# esquema.net
KiCad netlist of a schematic drawn in EAGLE
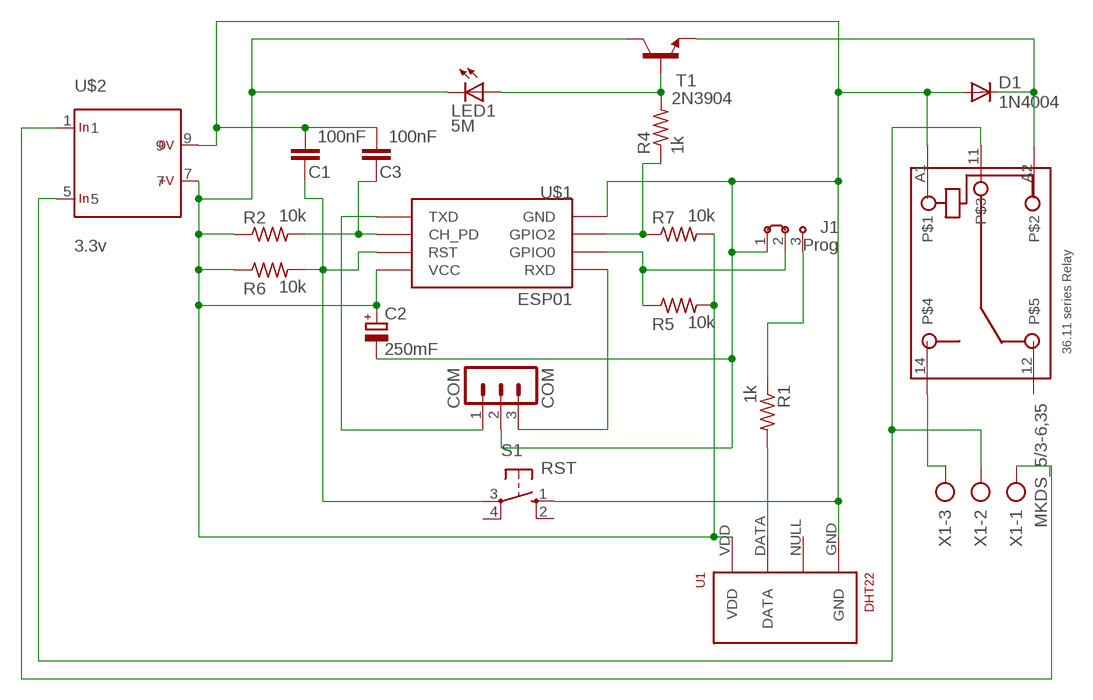
[diagram p0: schematic, sheet 1]

(export (version "E")
  (design (tool "Eeschema 10.0.6"))
  (components
    (comp (ref "C1")
      (value "100nF")
      (footprint "eagle-import:CAP-PTH-SMALL-KIT")
      (libsource (lib "eagle-import") (part "0.1UF-50V-20%(PTH)KIT-EZ"))
    )
    (comp (ref "C2")
      (value "250mF")
      (footprint "eagle-import:E2-5")
      (libsource (lib "eagle-import") (part "CPOL-EUE2-5"))
    )
    (comp (ref "C3")
      (value "100nF")
      (footprint "eagle-import:CAP-PTH-SMALL-KIT")
      (libsource (lib "eagle-import") (part "0.1UF-50V-20%(PTH)KIT-EZ"))
    )
    (comp (ref "COM")
      (value "COM")
      (footprint "eagle-import:MA03-1")
      (fields
        (field (name "MF") "MOLEX")
        (field (name "MPN") "47053-1000")
        (field (name "OC_FARNELL") "2313705")
      )
      (libsource (lib "eagle-import") (part "MA03-1"))
    )
    (comp (ref "D1")
      (value "1N4004")
      (footprint "eagle-import:DO41-10")
      (fields (field (name "MF") "VISHAY") (field (name "MPN") "1N4004-E3/54"))
      (libsource (lib "eagle-import") (part "1N4004"))
    )
    (comp (ref "J1")
      (value "Prog")
      (footprint "eagle-import:04C")
      (libsource (lib "eagle-import") (part "J2X2MM"))
    )
    (comp (ref "K1")
      (value "36.11")
      (footprint "eagle-import:36.11")
      (libsource (lib "eagle-import") (part "36.11"))
    )
    (comp (ref "LED1")
      (value "5M")
      (footprint "eagle-import:LED3MM")
      (fields (field (name "MF") "VISHAY") (field (name "MPN") "HVR3700001504JA100"))
      (libsource (lib "eagle-import") (part "LED3MM"))
    )
    (comp (ref "R1")
      (value "1k")
      (footprint "eagle-import:0204_5")
      (fields (field (name "MF") "MULTICOMP") (field (name "MPN") "MCF 0.25W 1K"))
      (libsource (lib "eagle-import") (part "R-US_0204/5"))
    )
    (comp (ref "R2")
      (value "10k")
      (footprint "eagle-import:0204_5")
      (fields (field (name "MF") "MULTICOMP") (field (name "MPN") "MCF 0.25W 10K"))
      (libsource (lib "eagle-import") (part "R-US_0204/5"))
    )
    (comp (ref "R4")
      (value "1k")
      (footprint "eagle-import:0204_5")
      (fields (field (name "MF") "MULTICOMP") (field (name "MPN") "MCF 0.25W 10K"))
      (libsource (lib "eagle-import") (part "R-US_0204/5"))
    )
    (comp (ref "R5")
      (value "10k")
      (footprint "eagle-import:0204_5")
      (fields (field (name "MF") "MULTICOMP") (field (name "MPN") "MCF 0.25W 10K"))
      (libsource (lib "eagle-import") (part "R-US_0204/5"))
    )
    (comp (ref "R6")
      (value "10k")
      (footprint "eagle-import:0204_5")
      (fields (field (name "MF") "MULTICOMP") (field (name "MPN") "MCF 0.25W 10K"))
      (libsource (lib "eagle-import") (part "R-US_0204/5"))
    )
    (comp (ref "R7")
      (value "10k")
      (footprint "eagle-import:0204_5")
      (fields (field (name "MF") "MULTICOMP") (field (name "MPN") "MCF 0.25W 10K"))
      (libsource (lib "eagle-import") (part "R-US_0204/5"))
    )
    (comp (ref "S1")
      (value "RST")
      (footprint "eagle-import:B3F-10XX")
      (fields (field (name "MPN") "B3F-1000"))
      (libsource (lib "eagle-import") (part "10-XX"))
    )
    (comp (ref "T1")
      (value "2N3904")
      (footprint "eagle-import:TO92")
      (fields (field (name "MF") "MULTICOMP"))
      (libsource (lib "eagle-import") (part "2N3904"))
    )
    (comp (ref "U$1")
      (value "ESP01")
      (footprint "eagle-import:ESP01")
      (libsource (lib "eagle-import") (part "ESP01"))
    )
    (comp (ref "U$2")
      (value "3.3v")
      (footprint "eagle-import:1")
      (fields (field (name "MF") "MYRRA") (field (name "MPN") "47121"))
      (libsource (lib "eagle-import") (part "SINGLE"))
    )
    (comp (ref "U1")
      (value "DHT22")
      (footprint "eagle-import:RHT03_DHT-22")
      (libsource (lib "eagle-import") (part "RHT03_DHT-22_AM2302"))
    )
    (comp (ref "X1")
      (value "MKDS_5/3-6,35")
      (footprint "eagle-import:MKDS_5_3-635")
      (fields (field (name "MF") "FARNELL") (field (name "MPN") "1714968"))
      (libsource (lib "eagle-import") (part "MKDS_5/3-6,35"))
    )
  )
  (nets
    (net (code "1") (name "Net-(C3-Pad1)") (class "Default")
      (node (ref "C3") (pin "1") (pinfunction "1_1") (pintype "passive"))
      (node (ref "R2") (pin "2") (pinfunction "2_2") (pintype "passive"))
      (node (ref "U$1") (pin "CH_PD") (pinfunction "CH_PD_CH_PD") (pintype "bidirectional"))
    )
    (net (code "2") (name "Net-(J1-Pad2)") (class "Default")
      (node (ref "J1") (pin "2") (pinfunction "2_2") (pintype "passive"))
      (node (ref "R5") (pin "1") (pinfunction "1_1") (pintype "passive"))
      (node (ref "U$1") (pin "GPIO0") (pinfunction "GPIO0_GPIO0") (pintype "bidirectional"))
    )
    (net (code "3") (name "Net-(J1-Pad3)") (class "Default")
      (node (ref "J1") (pin "3") (pinfunction "3_3") (pintype "passive"))
      (node (ref "R1") (pin "1") (pinfunction "1_1") (pintype "passive"))
    )
    (net (code "4") (name "Net-(K1-P$1)") (class "Default")
      (node (ref "C1") (pin "2") (pinfunction "2_2") (pintype "passive"))
      (node (ref "C2") (pin "-") (pinfunction "-_-") (pintype "passive"))
      (node (ref "C3") (pin "2") (pinfunction "2_2") (pintype "passive"))
      (node (ref "COM") (pin "2") (pinfunction "2_2") (pintype "passive"))
      (node (ref "D1") (pin "A") (pinfunction "A_A") (pintype "passive"))
      (node (ref "J1") (pin "1") (pinfunction "1_1") (pintype "passive"))
      (node (ref "K1") (pin "A1") (pinfunction "P$1_A1") (pintype "passive"))
      (node (ref "S1") (pin "1") (pinfunction "S_1") (pintype "passive"))
      (node (ref "U$1") (pin "GND") (pinfunction "GND_GND") (pintype "bidirectional"))
      (node (ref "U$2") (pin "9") (pinfunction "9_9") (pintype "output"))
      (node (ref "U1") (pin "GND") (pinfunction "GND_GND") (pintype "power_in"))
    )
    (net (code "5") (name "Net-(K1-P$2)") (class "Default")
      (node (ref "D1") (pin "C") (pinfunction "C_C") (pintype "passive"))
      (node (ref "K1") (pin "A2") (pinfunction "P$2_A2") (pintype "passive"))
      (node (ref "T1") (pin "3") (pinfunction "E_3") (pintype "passive"))
    )
    (net (code "6") (name "Net-(K1-P$3)") (class "Default")
      (node (ref "K1") (pin "11") (pinfunction "P$3_11") (pintype "passive"))
      (node (ref "U$2") (pin "5") (pinfunction "5_5") (pintype "input"))
      (node (ref "X1") (pin "2") (pinfunction "KL_2") (pintype "passive"))
    )
    (net (code "7") (name "Net-(K1-P$4)") (class "Default")
      (node (ref "K1") (pin "14") (pinfunction "P$4_14") (pintype "passive"))
      (node (ref "X1") (pin "3") (pinfunction "KL_3") (pintype "passive"))
    )
    (net (code "8") (name "Net-(LED1-C)") (class "Default")
      (node (ref "C2") (pin "+") (pinfunction "+_+") (pintype "passive"))
      (node (ref "LED1") (pin "K") (pinfunction "C_K") (pintype "passive"))
      (node (ref "R2") (pin "1") (pinfunction "1_1") (pintype "passive"))
      (node (ref "R5") (pin "2") (pinfunction "2_2") (pintype "passive"))
      (node (ref "R6") (pin "1") (pinfunction "1_1") (pintype "passive"))
      (node (ref "R7") (pin "2") (pinfunction "2_2") (pintype "passive"))
      (node (ref "T1") (pin "1") (pinfunction "C_1") (pintype "passive"))
      (node (ref "U$1") (pin "VCC") (pinfunction "VCC_VCC") (pintype "bidirectional"))
      (node (ref "U$2") (pin "7") (pinfunction "7_7") (pintype "output"))
      (node (ref "U1") (pin "VDD") (pinfunction "VDD_VDD") (pintype "power_in"))
    )
    (net (code "9") (name "Net-(R1-Pad2)") (class "Default")
      (node (ref "R1") (pin "2") (pinfunction "2_2") (pintype "passive"))
      (node (ref "U1") (pin "DATA") (pinfunction "DATA_DATA") (pintype "bidirectional"))
    )
    (net (code "10") (name "Net-(R4-Pad1)") (class "Default")
      (node (ref "R4") (pin "1") (pinfunction "1_1") (pintype "passive"))
      (node (ref "R7") (pin "1") (pinfunction "1_1") (pintype "passive"))
      (node (ref "U$1") (pin "GPIO2") (pinfunction "GPIO2_GPIO2") (pintype "bidirectional"))
    )
    (net (code "11") (name "Net-(S1-P)") (class "Default")
      (node (ref "C1") (pin "1") (pinfunction "1_1") (pintype "passive"))
      (node (ref "R6") (pin "2") (pinfunction "2_2") (pintype "passive"))
      (node (ref "S1") (pin "3") (pinfunction "P_3") (pintype "passive"))
      (node (ref "U$1") (pin "RST") (pinfunction "RST_RST") (pintype "bidirectional"))
    )
    (net (code "12") (name "Net-(T1-B)") (class "Default")
      (node (ref "LED1") (pin "A") (pinfunction "A_A") (pintype "passive"))
      (node (ref "R4") (pin "2") (pinfunction "2_2") (pintype "passive"))
      (node (ref "T1") (pin "2") (pinfunction "B_2") (pintype "passive"))
    )
    (net (code "13") (name "Net-(U$1-RXD)") (class "Default")
      (node (ref "COM") (pin "3") (pinfunction "3_3") (pintype "passive"))
      (node (ref "U$1") (pin "RX") (pinfunction "RXD_RX") (pintype "bidirectional"))
    )
    (net (code "14") (name "Net-(U$1-TXD)") (class "Default")
      (node (ref "COM") (pin "1") (pinfunction "1_1") (pintype "passive"))
      (node (ref "U$1") (pin "TX") (pinfunction "TXD_TX") (pintype "bidirectional"))
    )
    (net (code "15") (name "Net-(X1A-KL)") (class "Default")
      (node (ref "U$2") (pin "1") (pinfunction "1_1") (pintype "input"))
      (node (ref "X1") (pin "1") (pinfunction "KL_1") (pintype "passive"))
    )
    (net (code "16") (name "unconnected-(K1-P$5-Pad12)") (class "Default")
      (node (ref "K1") (pin "12") (pinfunction "P$5_12") (pintype "passive"))
    )
    (net (code "17") (name "unconnected-(S1-P1-Pad4)") (class "Default")
      (node (ref "S1") (pin "4") (pinfunction "P1_4") (pintype "passive"))
    )
    (net (code "18") (name "unconnected-(S1-S1-Pad2)") (class "Default")
      (node (ref "S1") (pin "2") (pinfunction "S1_2") (pintype "passive"))
    )
    (net (code "19") (name "unconnected-(U1-PadNULL)") (class "Default")
      (node (ref "U1") (pin "NULL") (pinfunction "NULL_NULL") (pintype "no_connect"))
    )
  )
)
